# 4bit_CPU.net
KiCad netlist of a schematic drawn in EAGLE
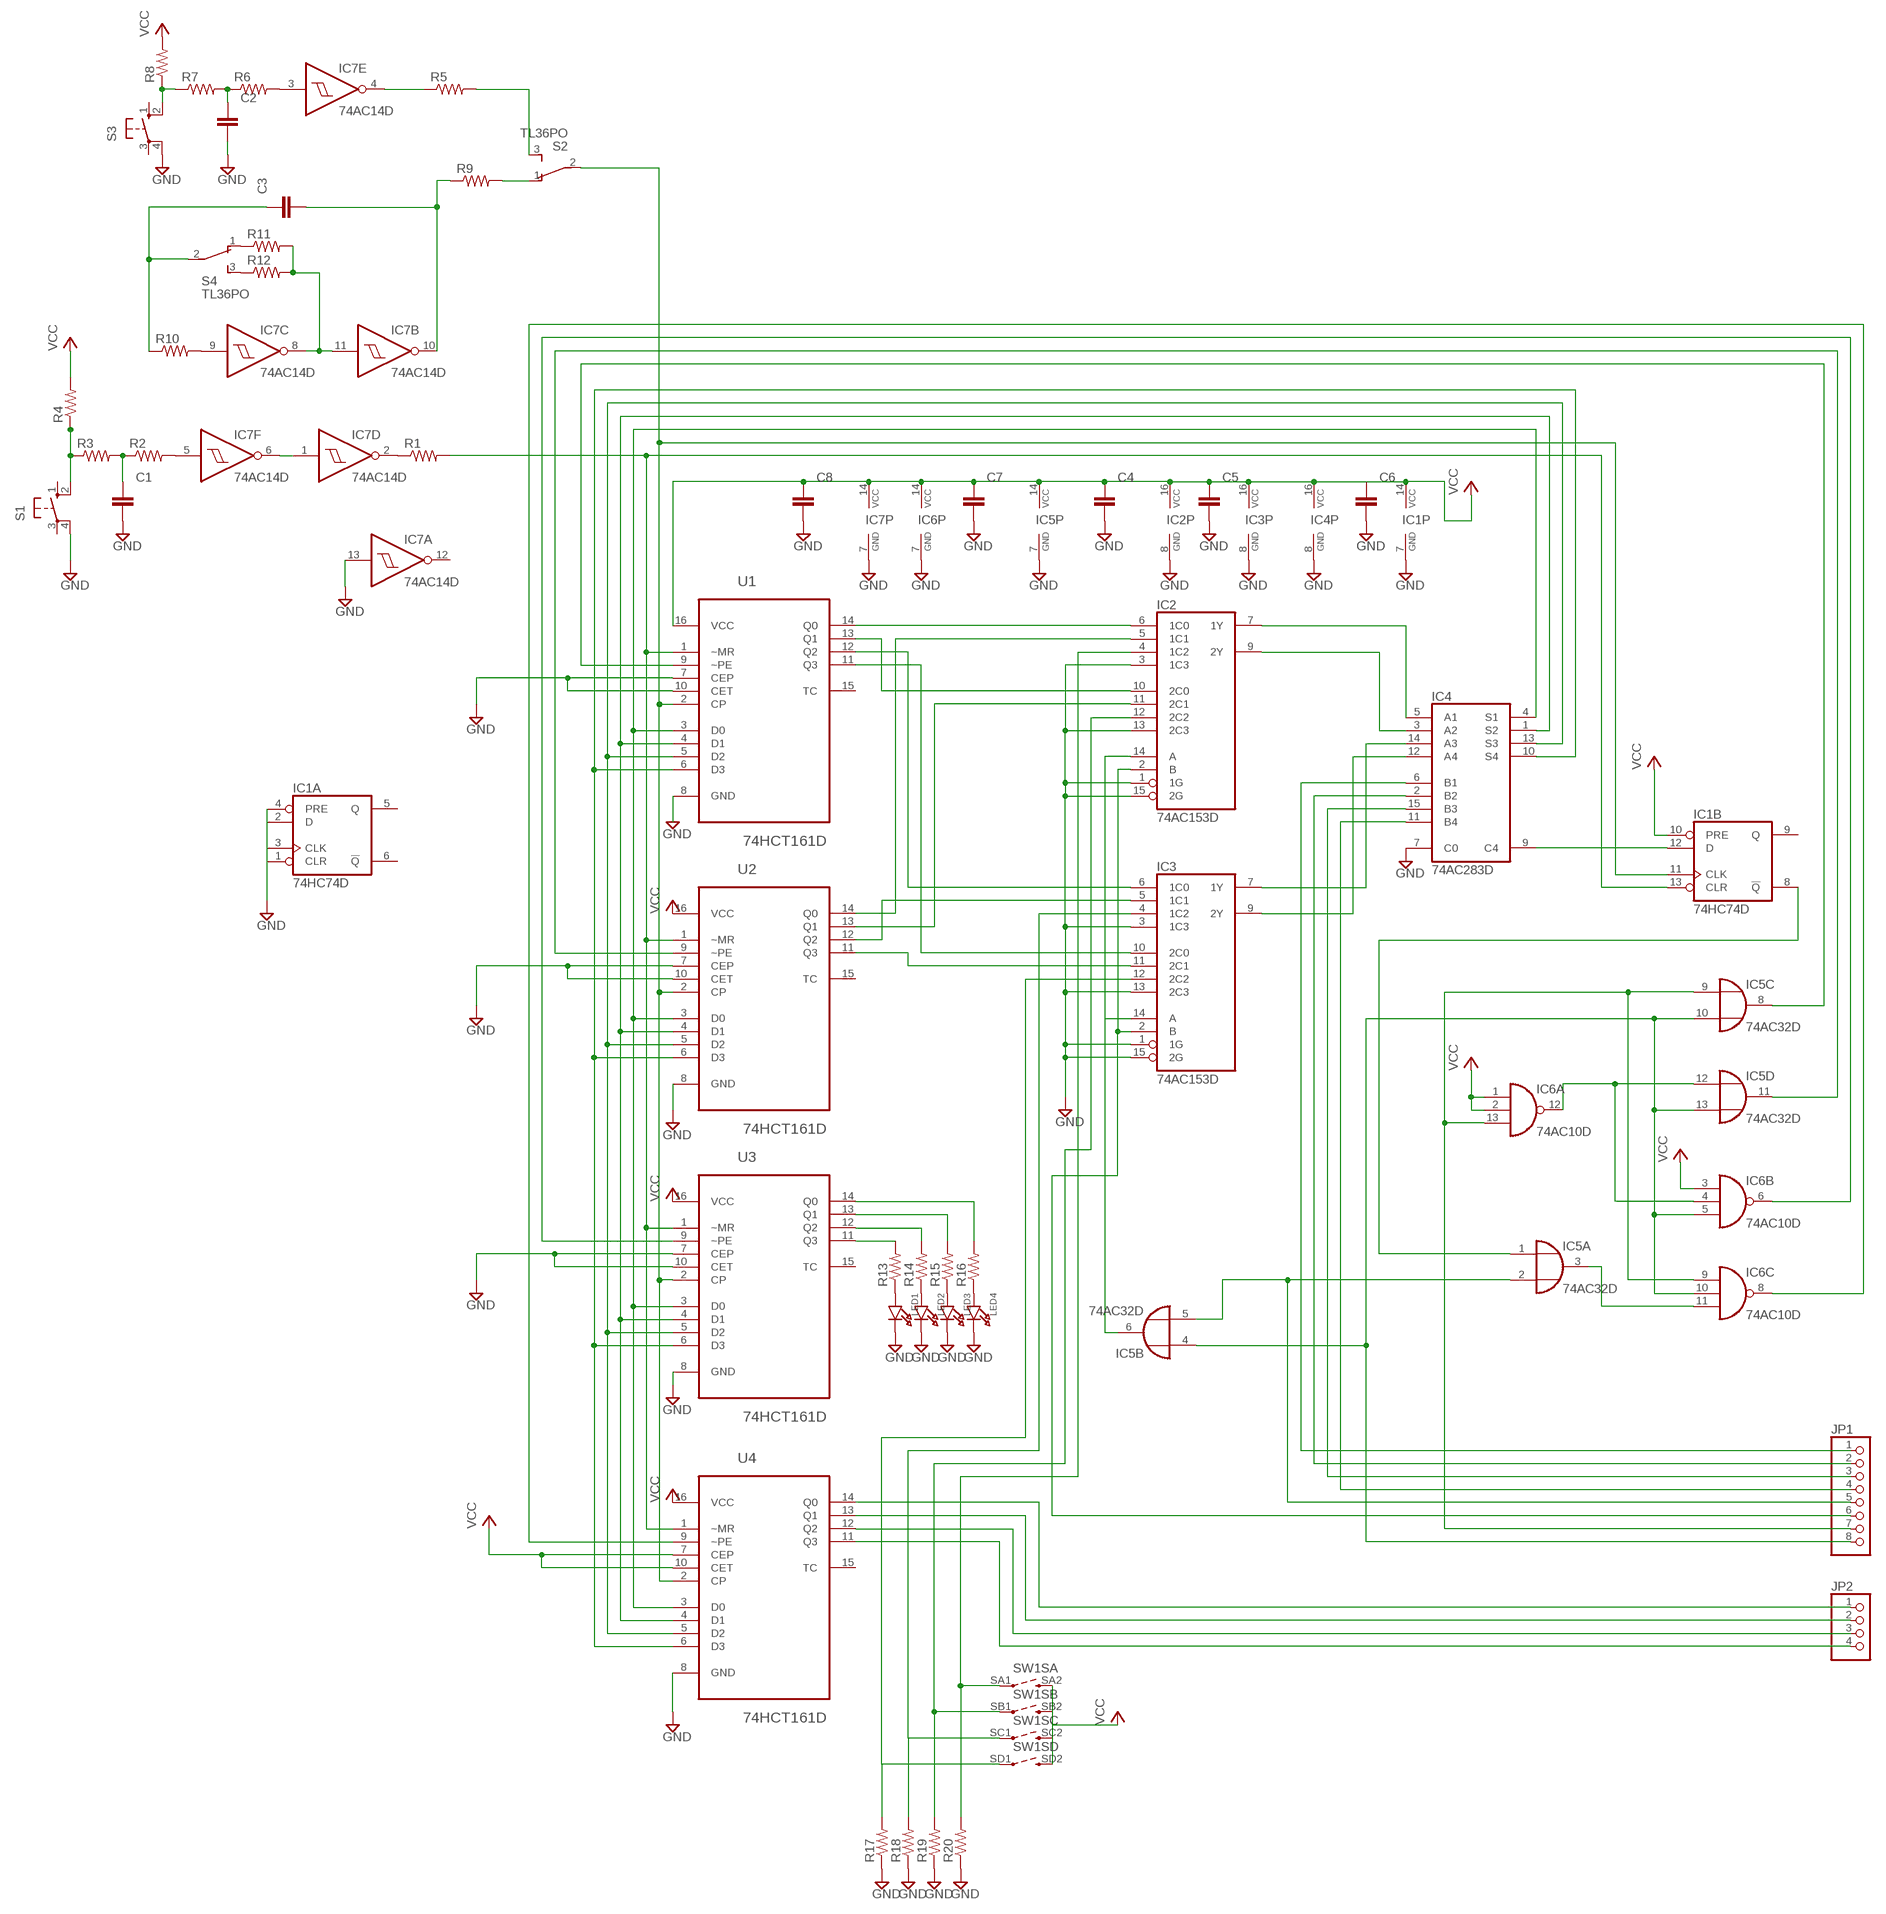
[diagram p0: schematic, sheet 1]

(export (version "E")
  (design (tool "Eeschema 10.0.6"))
  (components
    (comp (ref "C1")
      (value "CAPACITOR_NPOL-0603")
      (footprint "eagle-import:C603")
      (libsource (lib "eagle-import") (part "CAPACITOR_NPOL-0603"))
    )
    (comp (ref "C2")
      (value "CAPACITOR_NPOL-0603")
      (footprint "eagle-import:C603")
      (libsource (lib "eagle-import") (part "CAPACITOR_NPOL-0603"))
    )
    (comp (ref "C3")
      (value "CAPACITOR_NPOL-0603")
      (footprint "eagle-import:C603")
      (libsource (lib "eagle-import") (part "CAPACITOR_NPOL-0603"))
    )
    (comp (ref "C4")
      (value "CAPACITOR_NPOL-0603")
      (footprint "eagle-import:C603")
      (libsource (lib "eagle-import") (part "CAPACITOR_NPOL-0603"))
    )
    (comp (ref "C5")
      (value "CAPACITOR_NPOL-0603")
      (footprint "eagle-import:C603")
      (libsource (lib "eagle-import") (part "CAPACITOR_NPOL-0603"))
    )
    (comp (ref "C6")
      (value "CAPACITOR_NPOL-0603")
      (footprint "eagle-import:C603")
      (libsource (lib "eagle-import") (part "CAPACITOR_NPOL-0603"))
    )
    (comp (ref "C7")
      (value "CAPACITOR_NPOL-0603")
      (footprint "eagle-import:C603")
      (libsource (lib "eagle-import") (part "CAPACITOR_NPOL-0603"))
    )
    (comp (ref "C8")
      (value "CAPACITOR_NPOL-0603")
      (footprint "eagle-import:C603")
      (libsource (lib "eagle-import") (part "CAPACITOR_NPOL-0603"))
    )
    (comp (ref "IC1")
      (value "74HC74D")
      (footprint "eagle-import:SO14")
      (libsource (lib "eagle-import") (part "7474DHC"))
    )
    (comp (ref "IC2")
      (value "74AC153D")
      (footprint "eagle-import:SO16")
      (libsource (lib "eagle-import") (part "74153DAC"))
    )
    (comp (ref "IC3")
      (value "74AC153D")
      (footprint "eagle-import:SO16")
      (libsource (lib "eagle-import") (part "74153DAC"))
    )
    (comp (ref "IC4")
      (value "74AC283D")
      (footprint "eagle-import:SO16")
      (libsource (lib "eagle-import") (part "74283DAC"))
    )
    (comp (ref "IC5")
      (value "74AC32D")
      (footprint "eagle-import:SO14")
      (libsource (lib "eagle-import") (part "7432DAC"))
    )
    (comp (ref "IC6")
      (value "74AC10D")
      (footprint "eagle-import:SO14")
      (libsource (lib "eagle-import") (part "7410DAC"))
    )
    (comp (ref "IC7")
      (value "74AC14D")
      (footprint "eagle-import:SO14")
      (libsource (lib "eagle-import") (part "7414DAC"))
    )
    (comp (ref "JP1")
      (value "HEADER-1X8")
      (footprint "eagle-import:1X08_OVAL")
      (libsource (lib "eagle-import") (part "HEADER-1X8"))
    )
    (comp (ref "JP2")
      (value "HEADER-1X4")
      (footprint "eagle-import:1X04_OVAL")
      (libsource (lib "eagle-import") (part "HEADER-1X4"))
    )
    (comp (ref "LED1")
      (value "LED0603")
      (footprint "eagle-import:CHIPLED_0603")
      (libsource (lib "eagle-import") (part "LED0603"))
    )
    (comp (ref "LED2")
      (value "LED0603")
      (footprint "eagle-import:CHIPLED_0603")
      (libsource (lib "eagle-import") (part "LED0603"))
    )
    (comp (ref "LED3")
      (value "LED0603")
      (footprint "eagle-import:CHIPLED_0603")
      (libsource (lib "eagle-import") (part "LED0603"))
    )
    (comp (ref "LED4")
      (value "LED0603")
      (footprint "eagle-import:CHIPLED_0603")
      (libsource (lib "eagle-import") (part "LED0603"))
    )
    (comp (ref "R1")
      (value "R-US_R0603")
      (footprint "eagle-import:R0603")
      (libsource (lib "eagle-import") (part "R-US_R0603"))
    )
    (comp (ref "R2")
      (value "R-US_R0603")
      (footprint "eagle-import:R0603")
      (libsource (lib "eagle-import") (part "R-US_R0603"))
    )
    (comp (ref "R3")
      (value "R-US_R0603")
      (footprint "eagle-import:R0603")
      (libsource (lib "eagle-import") (part "R-US_R0603"))
    )
    (comp (ref "R4")
      (value "R-US_R0603")
      (footprint "eagle-import:R0603")
      (libsource (lib "eagle-import") (part "R-US_R0603"))
    )
    (comp (ref "R5")
      (value "R-US_R0603")
      (footprint "eagle-import:R0603")
      (libsource (lib "eagle-import") (part "R-US_R0603"))
    )
    (comp (ref "R6")
      (value "R-US_R0603")
      (footprint "eagle-import:R0603")
      (libsource (lib "eagle-import") (part "R-US_R0603"))
    )
    (comp (ref "R7")
      (value "R-US_R0603")
      (footprint "eagle-import:R0603")
      (libsource (lib "eagle-import") (part "R-US_R0603"))
    )
    (comp (ref "R8")
      (value "R-US_R0603")
      (footprint "eagle-import:R0603")
      (libsource (lib "eagle-import") (part "R-US_R0603"))
    )
    (comp (ref "R9")
      (value "R-US_R0603")
      (footprint "eagle-import:R0603")
      (libsource (lib "eagle-import") (part "R-US_R0603"))
    )
    (comp (ref "R10")
      (value "R-US_R0603")
      (footprint "eagle-import:R0603")
      (libsource (lib "eagle-import") (part "R-US_R0603"))
    )
    (comp (ref "R11")
      (value "R-US_R0603")
      (footprint "eagle-import:R0603")
      (libsource (lib "eagle-import") (part "R-US_R0603"))
    )
    (comp (ref "R12")
      (value "R-US_R0603")
      (footprint "eagle-import:R0603")
      (libsource (lib "eagle-import") (part "R-US_R0603"))
    )
    (comp (ref "R13")
      (value "R-US_R0603")
      (footprint "eagle-import:R0603")
      (libsource (lib "eagle-import") (part "R-US_R0603"))
    )
    (comp (ref "R14")
      (value "R-US_R0603")
      (footprint "eagle-import:R0603")
      (libsource (lib "eagle-import") (part "R-US_R0603"))
    )
    (comp (ref "R15")
      (value "R-US_R0603")
      (footprint "eagle-import:R0603")
      (libsource (lib "eagle-import") (part "R-US_R0603"))
    )
    (comp (ref "R16")
      (value "R-US_R0603")
      (footprint "eagle-import:R0603")
      (libsource (lib "eagle-import") (part "R-US_R0603"))
    )
    (comp (ref "R17")
      (value "R-US_R0603")
      (footprint "eagle-import:R0603")
      (libsource (lib "eagle-import") (part "R-US_R0603"))
    )
    (comp (ref "R18")
      (value "R-US_R0603")
      (footprint "eagle-import:R0603")
      (libsource (lib "eagle-import") (part "R-US_R0603"))
    )
    (comp (ref "R19")
      (value "R-US_R0603")
      (footprint "eagle-import:R0603")
      (libsource (lib "eagle-import") (part "R-US_R0603"))
    )
    (comp (ref "R20")
      (value "R-US_R0603")
      (footprint "eagle-import:R0603")
      (libsource (lib "eagle-import") (part "R-US_R0603"))
    )
    (comp (ref "S1")
      (value "10-XX")
      (footprint "eagle-import:B3F-10XX")
      (fields (field (name "MPN") "B3F-1000"))
      (libsource (lib "eagle-import") (part "10-XX"))
    )
    (comp (ref "S2")
      (value "TL36PO")
      (footprint "eagle-import:TL3XPO")
      (libsource (lib "eagle-import") (part "TL36PO"))
    )
    (comp (ref "S3")
      (value "10-XX")
      (footprint "eagle-import:B3F-10XX")
      (fields (field (name "MPN") "B3F-1000"))
      (libsource (lib "eagle-import") (part "10-XX"))
    )
    (comp (ref "S4")
      (value "TL36PO")
      (footprint "eagle-import:TL3XPO")
      (libsource (lib "eagle-import") (part "TL36PO"))
    )
    (comp (ref "SW1")
      (value "SW_DIP_4P")
      (footprint "eagle-import:SW-SMT-4")
      (libsource (lib "eagle-import") (part "SW_DIP_4P"))
    )
    (comp (ref "U1")
      (value "74HCT161D")
      (footprint "eagle-import:SOIC127P600X175-16N")
      (libsource (lib "eagle-import") (part "74HCT161D"))
    )
    (comp (ref "U2")
      (value "74HCT161D")
      (footprint "eagle-import:SOIC127P600X175-16N")
      (libsource (lib "eagle-import") (part "74HCT161D"))
    )
    (comp (ref "U3")
      (value "74HCT161D")
      (footprint "eagle-import:SOIC127P600X175-16N")
      (libsource (lib "eagle-import") (part "74HCT161D"))
    )
    (comp (ref "U4")
      (value "74HCT161D")
      (footprint "eagle-import:SOIC127P600X175-16N")
      (libsource (lib "eagle-import") (part "74HCT161D"))
    )
  )
  (nets
    (net (code "1") (name "GND") (class "Default")
      (node (ref "C1") (pin "2") (pinfunction "2_2") (pintype "passive"))
      (node (ref "C2") (pin "2") (pinfunction "2_2") (pintype "passive"))
      (node (ref "C4") (pin "2") (pinfunction "2_2") (pintype "passive"))
      (node (ref "C5") (pin "2") (pinfunction "2_2") (pintype "passive"))
      (node (ref "C6") (pin "2") (pinfunction "2_2") (pintype "passive"))
      (node (ref "C7") (pin "2") (pinfunction "2_2") (pintype "passive"))
      (node (ref "C8") (pin "2") (pinfunction "2_2") (pintype "passive"))
      (node (ref "IC1") (pin "1") (pinfunction "CLR_1") (pintype "input"))
      (node (ref "IC1") (pin "2") (pinfunction "D_2") (pintype "input"))
      (node (ref "IC1") (pin "3") (pinfunction "CLK_3") (pintype "input"))
      (node (ref "IC1") (pin "4") (pinfunction "PRE_4") (pintype "input"))
      (node (ref "IC1") (pin "7") (pinfunction "GND_7") (pintype "power_in"))
      (node (ref "IC2") (pin "1") (pinfunction "1G_1") (pintype "input"))
      (node (ref "IC2") (pin "13") (pinfunction "2C3_13") (pintype "input"))
      (node (ref "IC2") (pin "15") (pinfunction "2G_15") (pintype "input"))
      (node (ref "IC2") (pin "3") (pinfunction "1C3_3") (pintype "input"))
      (node (ref "IC2") (pin "8") (pinfunction "GND_8") (pintype "power_in"))
      (node (ref "IC3") (pin "1") (pinfunction "1G_1") (pintype "input"))
      (node (ref "IC3") (pin "13") (pinfunction "2C3_13") (pintype "input"))
      (node (ref "IC3") (pin "15") (pinfunction "2G_15") (pintype "input"))
      (node (ref "IC3") (pin "3") (pinfunction "1C3_3") (pintype "input"))
      (node (ref "IC3") (pin "8") (pinfunction "GND_8") (pintype "power_in"))
      (node (ref "IC4") (pin "7") (pinfunction "C0_7") (pintype "input"))
      (node (ref "IC4") (pin "8") (pinfunction "GND_8") (pintype "power_in"))
      (node (ref "IC5") (pin "7") (pinfunction "GND_7") (pintype "power_in"))
      (node (ref "IC6") (pin "7") (pinfunction "GND_7") (pintype "power_in"))
      (node (ref "IC7") (pin "13") (pinfunction "I_13") (pintype "input"))
      (node (ref "IC7") (pin "7") (pinfunction "GND_7") (pintype "power_in"))
      (node (ref "LED1") (pin "C") (pinfunction "C_C") (pintype "passive"))
      (node (ref "LED2") (pin "C") (pinfunction "C_C") (pintype "passive"))
      (node (ref "LED3") (pin "C") (pinfunction "C_C") (pintype "passive"))
      (node (ref "LED4") (pin "C") (pinfunction "C_C") (pintype "passive"))
      (node (ref "R17") (pin "1") (pinfunction "1_1") (pintype "passive"))
      (node (ref "R18") (pin "1") (pinfunction "1_1") (pintype "passive"))
      (node (ref "R19") (pin "1") (pinfunction "1_1") (pintype "passive"))
      (node (ref "R20") (pin "1") (pinfunction "1_1") (pintype "passive"))
      (node (ref "S1") (pin "4") (pinfunction "P1_4") (pintype "passive"))
      (node (ref "S3") (pin "4") (pinfunction "P1_4") (pintype "passive"))
      (node (ref "U1") (pin "10") (pinfunction "CET_10") (pintype "input"))
      (node (ref "U1") (pin "7") (pinfunction "CEP_7") (pintype "input"))
      (node (ref "U2") (pin "10") (pinfunction "CET_10") (pintype "input"))
      (node (ref "U2") (pin "7") (pinfunction "CEP_7") (pintype "input"))
      (node (ref "U2") (pin "8") (pinfunction "GND_8") (pintype "passive"))
      (node (ref "U3") (pin "10") (pinfunction "CET_10") (pintype "input"))
      (node (ref "U3") (pin "7") (pinfunction "CEP_7") (pintype "input"))
      (node (ref "U3") (pin "8") (pinfunction "GND_8") (pintype "passive"))
      (node (ref "U4") (pin "8") (pinfunction "GND_8") (pintype "passive"))
    )
    (net (code "2") (name "Net-(C1-Pad1)") (class "Default")
      (node (ref "C1") (pin "1") (pinfunction "1_1") (pintype "passive"))
      (node (ref "R2") (pin "1") (pinfunction "1_1") (pintype "passive"))
      (node (ref "R3") (pin "2") (pinfunction "2_2") (pintype "passive"))
    )
    (net (code "3") (name "Net-(C2-Pad1)") (class "Default")
      (node (ref "C2") (pin "1") (pinfunction "1_1") (pintype "passive"))
      (node (ref "R6") (pin "1") (pinfunction "1_1") (pintype "passive"))
      (node (ref "R7") (pin "2") (pinfunction "2_2") (pintype "passive"))
    )
    (net (code "4") (name "Net-(IC1B-CLK)") (class "Default")
      (node (ref "IC1") (pin "11") (pinfunction "CLK_11") (pintype "input"))
      (node (ref "S2") (pin "2") (pinfunction "P_2") (pintype "passive"))
      (node (ref "U1") (pin "2") (pinfunction "CP_2") (pintype "input"))
      (node (ref "U2") (pin "2") (pinfunction "CP_2") (pintype "input"))
      (node (ref "U3") (pin "2") (pinfunction "CP_2") (pintype "input"))
      (node (ref "U4") (pin "2") (pinfunction "CP_2") (pintype "input"))
    )
    (net (code "5") (name "Net-(IC1B-CLR)") (class "Default")
      (node (ref "IC1") (pin "13") (pinfunction "CLR_13") (pintype "input"))
      (node (ref "R1") (pin "2") (pinfunction "2_2") (pintype "passive"))
      (node (ref "U1") (pin "1") (pinfunction "~{MR}_1") (pintype "input"))
      (node (ref "U2") (pin "1") (pinfunction "~{MR}_1") (pintype "input"))
      (node (ref "U3") (pin "1") (pinfunction "~{MR}_1") (pintype "input"))
      (node (ref "U4") (pin "1") (pinfunction "~{MR}_1") (pintype "input"))
    )
    (net (code "6") (name "Net-(IC1B-D)") (class "Default")
      (node (ref "IC1") (pin "12") (pinfunction "D_12") (pintype "input"))
      (node (ref "IC4") (pin "9") (pinfunction "C4_9") (pintype "output"))
    )
    (net (code "7") (name "Net-(IC1B-~{Q})") (class "Default")
      (node (ref "IC1") (pin "8") (pinfunction "~{Q}_8") (pintype "output"))
      (node (ref "IC5") (pin "1") (pinfunction "I0_1") (pintype "input"))
    )
    (net (code "8") (name "Net-(IC2A-1C0)") (class "Default")
      (node (ref "IC2") (pin "6") (pinfunction "1C0_6") (pintype "input"))
      (node (ref "U1") (pin "14") (pinfunction "Q0_14") (pintype "output"))
    )
    (net (code "9") (name "Net-(IC2A-1C1)") (class "Default")
      (node (ref "IC2") (pin "5") (pinfunction "1C1_5") (pintype "input"))
      (node (ref "U2") (pin "14") (pinfunction "Q0_14") (pintype "output"))
    )
    (net (code "10") (name "Net-(IC2A-1C2)") (class "Default")
      (node (ref "IC2") (pin "4") (pinfunction "1C2_4") (pintype "input"))
      (node (ref "R20") (pin "2") (pinfunction "2_2") (pintype "passive"))
      (node (ref "SW1") (pin "SA1") (pinfunction "1_SA1") (pintype "passive"))
    )
    (net (code "11") (name "Net-(IC2A-1Y)") (class "Default")
      (node (ref "IC2") (pin "7") (pinfunction "1Y_7") (pintype "output"))
      (node (ref "IC4") (pin "5") (pinfunction "A1_5") (pintype "input"))
    )
    (net (code "12") (name "Net-(IC2A-2C0)") (class "Default")
      (node (ref "IC2") (pin "10") (pinfunction "2C0_10") (pintype "input"))
      (node (ref "U1") (pin "13") (pinfunction "Q1_13") (pintype "output"))
    )
    (net (code "13") (name "Net-(IC2A-2C1)") (class "Default")
      (node (ref "IC2") (pin "11") (pinfunction "2C1_11") (pintype "input"))
      (node (ref "U2") (pin "13") (pinfunction "Q1_13") (pintype "output"))
    )
    (net (code "14") (name "Net-(IC2A-2C2)") (class "Default")
      (node (ref "IC2") (pin "12") (pinfunction "2C2_12") (pintype "input"))
      (node (ref "R19") (pin "2") (pinfunction "2_2") (pintype "passive"))
      (node (ref "SW1") (pin "SB1") (pinfunction "1_SB1") (pintype "passive"))
    )
    (net (code "15") (name "Net-(IC2A-2Y)") (class "Default")
      (node (ref "IC2") (pin "9") (pinfunction "2Y_9") (pintype "output"))
      (node (ref "IC4") (pin "3") (pinfunction "A2_3") (pintype "input"))
    )
    (net (code "16") (name "Net-(IC2A-A)") (class "Default")
      (node (ref "IC2") (pin "14") (pinfunction "A_14") (pintype "input"))
      (node (ref "IC3") (pin "14") (pinfunction "A_14") (pintype "input"))
      (node (ref "IC5") (pin "6") (pinfunction "O_6") (pintype "output"))
    )
    (net (code "17") (name "Net-(IC2A-B)") (class "Default")
      (node (ref "IC2") (pin "2") (pinfunction "B_2") (pintype "input"))
      (node (ref "IC3") (pin "2") (pinfunction "B_2") (pintype "input"))
      (node (ref "JP1") (pin "6") (pinfunction "6_6") (pintype "passive"))
    )
    (net (code "18") (name "Net-(IC3A-1C0)") (class "Default")
      (node (ref "IC3") (pin "6") (pinfunction "1C0_6") (pintype "input"))
      (node (ref "U1") (pin "12") (pinfunction "Q2_12") (pintype "output"))
    )
    (net (code "19") (name "Net-(IC3A-1C1)") (class "Default")
      (node (ref "IC3") (pin "5") (pinfunction "1C1_5") (pintype "input"))
      (node (ref "U2") (pin "12") (pinfunction "Q2_12") (pintype "output"))
    )
    (net (code "20") (name "Net-(IC3A-1C2)") (class "Default")
      (node (ref "IC3") (pin "4") (pinfunction "1C2_4") (pintype "input"))
      (node (ref "R18") (pin "2") (pinfunction "2_2") (pintype "passive"))
      (node (ref "SW1") (pin "SC1") (pinfunction "1_SC1") (pintype "passive"))
    )
    (net (code "21") (name "Net-(IC3A-1Y)") (class "Default")
      (node (ref "IC3") (pin "7") (pinfunction "1Y_7") (pintype "output"))
      (node (ref "IC4") (pin "14") (pinfunction "A3_14") (pintype "input"))
    )
    (net (code "22") (name "Net-(IC3A-2C0)") (class "Default")
      (node (ref "IC3") (pin "10") (pinfunction "2C0_10") (pintype "input"))
      (node (ref "U1") (pin "11") (pinfunction "Q3_11") (pintype "output"))
    )
    (net (code "23") (name "Net-(IC3A-2C1)") (class "Default")
      (node (ref "IC3") (pin "11") (pinfunction "2C1_11") (pintype "input"))
      (node (ref "U2") (pin "11") (pinfunction "Q3_11") (pintype "output"))
    )
    (net (code "24") (name "Net-(IC3A-2C2)") (class "Default")
      (node (ref "IC3") (pin "12") (pinfunction "2C2_12") (pintype "input"))
      (node (ref "R17") (pin "2") (pinfunction "2_2") (pintype "passive"))
      (node (ref "SW1") (pin "SD1") (pinfunction "1_SD1") (pintype "passive"))
    )
    (net (code "25") (name "Net-(IC3A-2Y)") (class "Default")
      (node (ref "IC3") (pin "9") (pinfunction "2Y_9") (pintype "output"))
      (node (ref "IC4") (pin "12") (pinfunction "A4_12") (pintype "input"))
    )
    (net (code "26") (name "Net-(IC4A-B1)") (class "Default")
      (node (ref "IC4") (pin "6") (pinfunction "B1_6") (pintype "input"))
      (node (ref "JP1") (pin "1") (pinfunction "1_1") (pintype "passive"))
    )
    (net (code "27") (name "Net-(IC4A-B2)") (class "Default")
      (node (ref "IC4") (pin "2") (pinfunction "B2_2") (pintype "input"))
      (node (ref "JP1") (pin "2") (pinfunction "2_2") (pintype "passive"))
    )
    (net (code "28") (name "Net-(IC4A-B3)") (class "Default")
      (node (ref "IC4") (pin "15") (pinfunction "B3_15") (pintype "input"))
      (node (ref "JP1") (pin "3") (pinfunction "3_3") (pintype "passive"))
    )
    (net (code "29") (name "Net-(IC4A-B4)") (class "Default")
      (node (ref "IC4") (pin "11") (pinfunction "B4_11") (pintype "input"))
      (node (ref "JP1") (pin "4") (pinfunction "4_4") (pintype "passive"))
    )
    (net (code "30") (name "Net-(IC4A-S1)") (class "Default")
      (node (ref "IC4") (pin "4") (pinfunction "S1_4") (pintype "output"))
      (node (ref "U1") (pin "3") (pinfunction "D0_3") (pintype "input"))
      (node (ref "U2") (pin "3") (pinfunction "D0_3") (pintype "input"))
      (node (ref "U3") (pin "3") (pinfunction "D0_3") (pintype "input"))
      (node (ref "U4") (pin "3") (pinfunction "D0_3") (pintype "input"))
    )
    (net (code "31") (name "Net-(IC4A-S2)") (class "Default")
      (node (ref "IC4") (pin "1") (pinfunction "S2_1") (pintype "output"))
      (node (ref "U1") (pin "4") (pinfunction "D1_4") (pintype "input"))
      (node (ref "U2") (pin "4") (pinfunction "D1_4") (pintype "input"))
      (node (ref "U3") (pin "4") (pinfunction "D1_4") (pintype "input"))
      (node (ref "U4") (pin "4") (pinfunction "D1_4") (pintype "input"))
    )
    (net (code "32") (name "Net-(IC4A-S3)") (class "Default")
      (node (ref "IC4") (pin "13") (pinfunction "S3_13") (pintype "output"))
      (node (ref "U1") (pin "5") (pinfunction "D2_5") (pintype "input"))
      (node (ref "U2") (pin "5") (pinfunction "D2_5") (pintype "input"))
      (node (ref "U3") (pin "5") (pinfunction "D2_5") (pintype "input"))
      (node (ref "U4") (pin "5") (pinfunction "D2_5") (pintype "input"))
    )
    (net (code "33") (name "Net-(IC4A-S4)") (class "Default")
      (node (ref "IC4") (pin "10") (pinfunction "S4_10") (pintype "output"))
      (node (ref "U1") (pin "6") (pinfunction "D3_6") (pintype "input"))
      (node (ref "U2") (pin "6") (pinfunction "D3_6") (pintype "input"))
      (node (ref "U3") (pin "6") (pinfunction "D3_6") (pintype "input"))
      (node (ref "U4") (pin "6") (pinfunction "D3_6") (pintype "input"))
    )
    (net (code "34") (name "Net-(IC5A-I1)") (class "Default")
      (node (ref "IC5") (pin "2") (pinfunction "I1_2") (pintype "input"))
      (node (ref "IC5") (pin "5") (pinfunction "I1_5") (pintype "input"))
      (node (ref "JP1") (pin "5") (pinfunction "5_5") (pintype "passive"))
    )
    (net (code "35") (name "Net-(IC5A-O)") (class "Default")
      (node (ref "IC5") (pin "3") (pinfunction "O_3") (pintype "output"))
      (node (ref "IC6") (pin "11") (pinfunction "I2_11") (pintype "input"))
    )
    (net (code "36") (name "Net-(IC5B-I0)") (class "Default")
      (node (ref "IC5") (pin "10") (pinfunction "I1_10") (pintype "input"))
      (node (ref "IC5") (pin "13") (pinfunction "I1_13") (pintype "input"))
      (node (ref "IC5") (pin "4") (pinfunction "I0_4") (pintype "input"))
      (node (ref "IC6") (pin "10") (pinfunction "I1_10") (pintype "input"))
      (node (ref "IC6") (pin "5") (pinfunction "I2_5") (pintype "input"))
      (node (ref "JP1") (pin "8") (pinfunction "8_8") (pintype "passive"))
    )
    (net (code "37") (name "Net-(IC5C-I0)") (class "Default")
      (node (ref "IC5") (pin "9") (pinfunction "I0_9") (pintype "input"))
      (node (ref "IC6") (pin "13") (pinfunction "I2_13") (pintype "input"))
      (node (ref "IC6") (pin "9") (pinfunction "I0_9") (pintype "input"))
      (node (ref "JP1") (pin "7") (pinfunction "7_7") (pintype "passive"))
    )
    (net (code "38") (name "Net-(IC5C-O)") (class "Default")
      (node (ref "IC5") (pin "8") (pinfunction "O_8") (pintype "output"))
      (node (ref "U1") (pin "9") (pinfunction "~{PE}_9") (pintype "input"))
    )
    (net (code "39") (name "Net-(IC5D-I0)") (class "Default")
      (node (ref "IC5") (pin "12") (pinfunction "I0_12") (pintype "input"))
      (node (ref "IC6") (pin "12") (pinfunction "O_12") (pintype "output"))
      (node (ref "IC6") (pin "4") (pinfunction "I1_4") (pintype "input"))
    )
    (net (code "40") (name "Net-(IC5D-O)") (class "Default")
      (node (ref "IC5") (pin "11") (pinfunction "O_11") (pintype "output"))
      (node (ref "U2") (pin "9") (pinfunction "~{PE}_9") (pintype "input"))
    )
    (net (code "41") (name "Net-(IC6B-O)") (class "Default")
      (node (ref "IC6") (pin "6") (pinfunction "O_6") (pintype "output"))
      (node (ref "U3") (pin "9") (pinfunction "~{PE}_9") (pintype "input"))
    )
    (net (code "42") (name "Net-(IC6C-O)") (class "Default")
      (node (ref "IC6") (pin "8") (pinfunction "O_8") (pintype "output"))
      (node (ref "U4") (pin "9") (pinfunction "~{PE}_9") (pintype "input"))
    )
    (net (code "43") (name "Net-(IC7B-I)") (class "Default")
      (node (ref "IC7") (pin "11") (pinfunction "I_11") (pintype "input"))
      (node (ref "IC7") (pin "8") (pinfunction "O_8") (pintype "output"))
      (node (ref "R11") (pin "2") (pinfunction "2_2") (pintype "passive"))
      (node (ref "R12") (pin "2") (pinfunction "2_2") (pintype "passive"))
    )
    (net (code "44") (name "Net-(IC7B-O)") (class "Default")
      (node (ref "C3") (pin "2") (pinfunction "2_2") (pintype "passive"))
      (node (ref "IC7") (pin "10") (pinfunction "O_10") (pintype "output"))
      (node (ref "R9") (pin "1") (pinfunction "1_1") (pintype "passive"))
    )
    (net (code "45") (name "Net-(IC7C-I)") (class "Default")
      (node (ref "IC7") (pin "9") (pinfunction "I_9") (pintype "input"))
      (node (ref "R10") (pin "2") (pinfunction "2_2") (pintype "passive"))
    )
    (net (code "46") (name "Net-(IC7D-I)") (class "Default")
      (node (ref "IC7") (pin "1") (pinfunction "I_1") (pintype "input"))
      (node (ref "IC7") (pin "6") (pinfunction "O_6") (pintype "output"))
    )
    (net (code "47") (name "Net-(IC7D-O)") (class "Default")
      (node (ref "IC7") (pin "2") (pinfunction "O_2") (pintype "output"))
      (node (ref "R1") (pin "1") (pinfunction "1_1") (pintype "passive"))
    )
    (net (code "48") (name "Net-(IC7E-I)") (class "Default")
      (node (ref "IC7") (pin "3") (pinfunction "I_3") (pintype "input"))
      (node (ref "R6") (pin "2") (pinfunction "2_2") (pintype "passive"))
    )
    (net (code "49") (name "Net-(IC7E-O)") (class "Default")
      (node (ref "IC7") (pin "4") (pinfunction "O_4") (pintype "output"))
      (node (ref "R5") (pin "1") (pinfunction "1_1") (pintype "passive"))
    )
    (net (code "50") (name "Net-(IC7F-I)") (class "Default")
      (node (ref "IC7") (pin "5") (pinfunction "I_5") (pintype "input"))
      (node (ref "R2") (pin "2") (pinfunction "2_2") (pintype "passive"))
    )
    (net (code "51") (name "Net-(LED1-PadA)") (class "Default")
      (node (ref "LED1") (pin "A") (pinfunction "A_A") (pintype "passive"))
      (node (ref "R13") (pin "1") (pinfunction "1_1") (pintype "passive"))
    )
    (net (code "52") (name "Net-(LED2-PadA)") (class "Default")
      (node (ref "LED2") (pin "A") (pinfunction "A_A") (pintype "passive"))
      (node (ref "R14") (pin "1") (pinfunction "1_1") (pintype "passive"))
    )
    (net (code "53") (name "Net-(LED3-PadA)") (class "Default")
      (node (ref "LED3") (pin "A") (pinfunction "A_A") (pintype "passive"))
      (node (ref "R15") (pin "1") (pinfunction "1_1") (pintype "passive"))
    )
    (net (code "54") (name "Net-(LED4-PadA)") (class "Default")
      (node (ref "LED4") (pin "A") (pinfunction "A_A") (pintype "passive"))
      (node (ref "R16") (pin "1") (pinfunction "1_1") (pintype "passive"))
    )
    (net (code "55") (name "Net-(S1-S1)") (class "Default")
      (node (ref "R3") (pin "1") (pinfunction "1_1") (pintype "passive"))
      (node (ref "R4") (pin "1") (pinfunction "1_1") (pintype "passive"))
      (node (ref "S1") (pin "2") (pinfunction "S1_2") (pintype "passive"))
    )
    (net (code "56") (name "Net-(S2-O)") (class "Default")
      (node (ref "R9") (pin "2") (pinfunction "2_2") (pintype "passive"))
      (node (ref "S2") (pin "1") (pinfunction "O_1") (pintype "passive"))
    )
    (net (code "57") (name "Net-(S2-S)") (class "Default")
      (node (ref "R5") (pin "2") (pinfunction "2_2") (pintype "passive"))
      (node (ref "S2") (pin "3") (pinfunction "S_3") (pintype "passive"))
    )
    (net (code "58") (name "Net-(S3-S1)") (class "Default")
      (node (ref "R7") (pin "1") (pinfunction "1_1") (pintype "passive"))
      (node (ref "R8") (pin "1") (pinfunction "1_1") (pintype "passive"))
      (node (ref "S3") (pin "2") (pinfunction "S1_2") (pintype "passive"))
    )
    (net (code "59") (name "Net-(S4-O)") (class "Default")
      (node (ref "R11") (pin "1") (pinfunction "1_1") (pintype "passive"))
      (node (ref "S4") (pin "1") (pinfunction "O_1") (pintype "passive"))
    )
    (net (code "60") (name "Net-(S4-P)") (class "Default")
      (node (ref "C3") (pin "1") (pinfunction "1_1") (pintype "passive"))
      (node (ref "R10") (pin "1") (pinfunction "1_1") (pintype "passive"))
      (node (ref "S4") (pin "2") (pinfunction "P_2") (pintype "passive"))
    )
    (net (code "61") (name "Net-(S4-S)") (class "Default")
      (node (ref "R12") (pin "1") (pinfunction "1_1") (pintype "passive"))
      (node (ref "S4") (pin "3") (pinfunction "S_3") (pintype "passive"))
    )
    (net (code "62") (name "Net-(U3-Q0)") (class "Default")
      (node (ref "R16") (pin "2") (pinfunction "2_2") (pintype "passive"))
      (node (ref "U3") (pin "14") (pinfunction "Q0_14") (pintype "output"))
    )
    (net (code "63") (name "Net-(U3-Q1)") (class "Default")
      (node (ref "R15") (pin "2") (pinfunction "2_2") (pintype "passive"))
      (node (ref "U3") (pin "13") (pinfunction "Q1_13") (pintype "output"))
    )
    (net (code "64") (name "Net-(U3-Q2)") (class "Default")
      (node (ref "R14") (pin "2") (pinfunction "2_2") (pintype "passive"))
      (node (ref "U3") (pin "12") (pinfunction "Q2_12") (pintype "output"))
    )
    (net (code "65") (name "Net-(U3-Q3)") (class "Default")
      (node (ref "R13") (pin "2") (pinfunction "2_2") (pintype "passive"))
      (node (ref "U3") (pin "11") (pinfunction "Q3_11") (pintype "output"))
    )
    (net (code "66") (name "Net-(U4-Q0)") (class "Default")
      (node (ref "JP2") (pin "1") (pinfunction "1_1") (pintype "passive"))
      (node (ref "U4") (pin "14") (pinfunction "Q0_14") (pintype "output"))
    )
    (net (code "67") (name "Net-(U4-Q1)") (class "Default")
      (node (ref "JP2") (pin "2") (pinfunction "2_2") (pintype "passive"))
      (node (ref "U4") (pin "13") (pinfunction "Q1_13") (pintype "output"))
    )
    (net (code "68") (name "Net-(U4-Q2)") (class "Default")
      (node (ref "JP2") (pin "3") (pinfunction "3_3") (pintype "passive"))
      (node (ref "U4") (pin "12") (pinfunction "Q2_12") (pintype "output"))
    )
    (net (code "69") (name "Net-(U4-Q3)") (class "Default")
      (node (ref "JP2") (pin "4") (pinfunction "4_4") (pintype "passive"))
      (node (ref "U4") (pin "11") (pinfunction "Q3_11") (pintype "output"))
    )
    (net (code "70") (name "VCC") (class "Default")
      (node (ref "C4") (pin "1") (pinfunction "1_1") (pintype "passive"))
      (node (ref "C5") (pin "1") (pinfunction "1_1") (pintype "passive"))
      (node (ref "C6") (pin "1") (pinfunction "1_1") (pintype "passive"))
      (node (ref "C7") (pin "1") (pinfunction "1_1") (pintype "passive"))
      (node (ref "C8") (pin "1") (pinfunction "1_1") (pintype "passive"))
      (node (ref "IC1") (pin "10") (pinfunction "PRE_10") (pintype "input"))
      (node (ref "IC1") (pin "14") (pinfunction "VCC_14") (pintype "power_in"))
      (node (ref "IC2") (pin "16") (pinfunction "VCC_16") (pintype "power_in"))
      (node (ref "IC3") (pin "16") (pinfunction "VCC_16") (pintype "power_in"))
      (node (ref "IC4") (pin "16") (pinfunction "VCC_16") (pintype "power_in"))
      (node (ref "IC5") (pin "14") (pinfunction "VCC_14") (pintype "power_in"))
      (node (ref "IC6") (pin "1") (pinfunction "I0_1") (pintype "input"))
      (node (ref "IC6") (pin "14") (pinfunction "VCC_14") (pintype "power_in"))
      (node (ref "IC6") (pin "2") (pinfunction "I1_2") (pintype "input"))
      (node (ref "IC6") (pin "3") (pinfunction "I0_3") (pintype "input"))
      (node (ref "IC7") (pin "14") (pinfunction "VCC_14") (pintype "power_in"))
      (node (ref "R4") (pin "2") (pinfunction "2_2") (pintype "passive"))
      (node (ref "R8") (pin "2") (pinfunction "2_2") (pintype "passive"))
      (node (ref "SW1") (pin "SA2") (pinfunction "2_SA2") (pintype "passive"))
      (node (ref "SW1") (pin "SB2") (pinfunction "2_SB2") (pintype "passive"))
      (node (ref "SW1") (pin "SC2") (pinfunction "2_SC2") (pintype "passive"))
      (node (ref "SW1") (pin "SD2") (pinfunction "2_SD2") (pintype "passive"))
      (node (ref "U1") (pin "16") (pinfunction "VCC_16") (pintype "power_in"))
      (node (ref "U2") (pin "16") (pinfunction "VCC_16") (pintype "power_in"))
      (node (ref "U3") (pin "16") (pinfunction "VCC_16") (pintype "power_in"))
      (node (ref "U4") (pin "10") (pinfunction "CET_10") (pintype "input"))
      (node (ref "U4") (pin "16") (pinfunction "VCC_16") (pintype "power_in"))
      (node (ref "U4") (pin "7") (pinfunction "CEP_7") (pintype "input"))
    )
    (net (code "71") (name "unconnected-(IC1A-Q-Pad5)") (class "Default")
      (node (ref "IC1") (pin "5") (pinfunction "Q_5") (pintype "output"))
    )
    (net (code "72") (name "unconnected-(IC1A-~{Q}-Pad6)") (class "Default")
      (node (ref "IC1") (pin "6") (pinfunction "~{Q}_6") (pintype "output"))
    )
    (net (code "73") (name "unconnected-(IC1B-Q-Pad9)") (class "Default")
      (node (ref "IC1") (pin "9") (pinfunction "Q_9") (pintype "output"))
    )
    (net (code "74") (name "unconnected-(IC7A-O-Pad12)") (class "Default")
      (node (ref "IC7") (pin "12") (pinfunction "O_12") (pintype "output"))
    )
    (net (code "75") (name "unconnected-(S1-P-Pad3)") (class "Default")
      (node (ref "S1") (pin "3") (pinfunction "P_3") (pintype "passive"))
    )
    (net (code "76") (name "unconnected-(S1-S-Pad1)") (class "Default")
      (node (ref "S1") (pin "1") (pinfunction "S_1") (pintype "passive"))
    )
    (net (code "77") (name "unconnected-(S3-P-Pad3)") (class "Default")
      (node (ref "S3") (pin "3") (pinfunction "P_3") (pintype "passive"))
    )
    (net (code "78") (name "unconnected-(S3-S-Pad1)") (class "Default")
      (node (ref "S3") (pin "1") (pinfunction "S_1") (pintype "passive"))
    )
    (net (code "79") (name "unconnected-(U1-GND-Pad8)") (class "Default")
      (node (ref "U1") (pin "8") (pinfunction "GND_8") (pintype "passive"))
    )
    (net (code "80") (name "unconnected-(U1-TC-Pad15)") (class "Default")
      (node (ref "U1") (pin "15") (pinfunction "TC_15") (pintype "output"))
    )
    (net (code "81") (name "unconnected-(U2-TC-Pad15)") (class "Default")
      (node (ref "U2") (pin "15") (pinfunction "TC_15") (pintype "output"))
    )
    (net (code "82") (name "unconnected-(U3-TC-Pad15)") (class "Default")
      (node (ref "U3") (pin "15") (pinfunction "TC_15") (pintype "output"))
    )
    (net (code "83") (name "unconnected-(U4-TC-Pad15)") (class "Default")
      (node (ref "U4") (pin "15") (pinfunction "TC_15") (pintype "output"))
    )
  )
)
